# Sheet1.net
KiCad netlist of a schematic drawn in Altium Designer
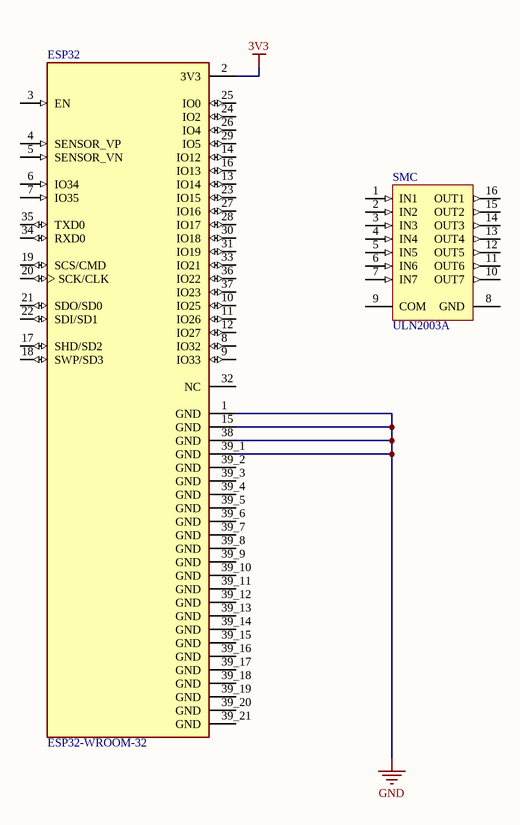
[diagram p0: Sheet1.SchDoc]

(export (version "E")
  (design (tool "Eeschema 10.0.6"))
  (components
    (comp (ref "ESP32")
      (value "ESP32-WROOM-32")
      (footprint "MODULE_ESP32-WROOM-32")
      (fields (field (name "MF") "Espressif Systems"))
      (libsource (lib "ESP32-WROOM-32") (part "ESP32-WROOM-32"))
    )
    (comp (ref "SMC")
      (value "ULN2003A")
      (footprint "STM-DIP-16L")
      (description "Seven Darlington Array, 50 V, 0.5 A, -40 to 85 degC, 16-Pin DIP, RoHS, Tube")
      (fields (field (name "MANUFACTURER") "STMicroelectronics"))
      (libsource (lib "Altium Content Vault") (part "STM-ULN2003A-PDIP-16"))
    )
  )
  (nets
    (net (code "1") (name "3V3") (class "Default")
      (node (ref "ESP32") (pin "2") (pinfunction "3V3_2") (pintype "power_in"))
    )
    (net (code "2") (name "GND") (class "Default")
      (node (ref "ESP32") (pin "1") (pinfunction "GND_1") (pintype "power_in"))
      (node (ref "ESP32") (pin "15") (pinfunction "GND_15") (pintype "power_in"))
      (node (ref "ESP32") (pin "38") (pinfunction "GND_38") (pintype "power_in"))
      (node (ref "ESP32") (pin "39_1") (pinfunction "GND_39_1") (pintype "power_in"))
    )
    (net (code "3") (name "unconnected-(ESP32-EN-Pad3)") (class "Default")
      (node (ref "ESP32") (pin "3") (pinfunction "EN_3") (pintype "input"))
    )
    (net (code "4") (name "unconnected-(ESP32-GND-Pad39_2)") (class "Default")
      (node (ref "ESP32") (pin "39_2") (pinfunction "GND_39_2") (pintype "power_in"))
    )
    (net (code "5") (name "unconnected-(ESP32-GND-Pad39_3)") (class "Default")
      (node (ref "ESP32") (pin "39_3") (pinfunction "GND_39_3") (pintype "power_in"))
    )
    (net (code "6") (name "unconnected-(ESP32-GND-Pad39_4)") (class "Default")
      (node (ref "ESP32") (pin "39_4") (pinfunction "GND_39_4") (pintype "power_in"))
    )
    (net (code "7") (name "unconnected-(ESP32-GND-Pad39_5)") (class "Default")
      (node (ref "ESP32") (pin "39_5") (pinfunction "GND_39_5") (pintype "power_in"))
    )
    (net (code "8") (name "unconnected-(ESP32-GND-Pad39_6)") (class "Default")
      (node (ref "ESP32") (pin "39_6") (pinfunction "GND_39_6") (pintype "power_in"))
    )
    (net (code "9") (name "unconnected-(ESP32-GND-Pad39_7)") (class "Default")
      (node (ref "ESP32") (pin "39_7") (pinfunction "GND_39_7") (pintype "power_in"))
    )
    (net (code "10") (name "unconnected-(ESP32-GND-Pad39_8)") (class "Default")
      (node (ref "ESP32") (pin "39_8") (pinfunction "GND_39_8") (pintype "power_in"))
    )
    (net (code "11") (name "unconnected-(ESP32-GND-Pad39_9)") (class "Default")
      (node (ref "ESP32") (pin "39_9") (pinfunction "GND_39_9") (pintype "power_in"))
    )
    (net (code "12") (name "unconnected-(ESP32-GND-Pad39_10)") (class "Default")
      (node (ref "ESP32") (pin "39_10") (pinfunction "GND_39_10") (pintype "power_in"))
    )
    (net (code "13") (name "unconnected-(ESP32-GND-Pad39_11)") (class "Default")
      (node (ref "ESP32") (pin "39_11") (pinfunction "GND_39_11") (pintype "power_in"))
    )
    (net (code "14") (name "unconnected-(ESP32-GND-Pad39_12)") (class "Default")
      (node (ref "ESP32") (pin "39_12") (pinfunction "GND_39_12") (pintype "power_in"))
    )
    (net (code "15") (name "unconnected-(ESP32-GND-Pad39_13)") (class "Default")
      (node (ref "ESP32") (pin "39_13") (pinfunction "GND_39_13") (pintype "power_in"))
    )
    (net (code "16") (name "unconnected-(ESP32-GND-Pad39_14)") (class "Default")
      (node (ref "ESP32") (pin "39_14") (pinfunction "GND_39_14") (pintype "power_in"))
    )
    (net (code "17") (name "unconnected-(ESP32-GND-Pad39_15)") (class "Default")
      (node (ref "ESP32") (pin "39_15") (pinfunction "GND_39_15") (pintype "power_in"))
    )
    (net (code "18") (name "unconnected-(ESP32-GND-Pad39_16)") (class "Default")
      (node (ref "ESP32") (pin "39_16") (pinfunction "GND_39_16") (pintype "power_in"))
    )
    (net (code "19") (name "unconnected-(ESP32-GND-Pad39_17)") (class "Default")
      (node (ref "ESP32") (pin "39_17") (pinfunction "GND_39_17") (pintype "power_in"))
    )
    (net (code "20") (name "unconnected-(ESP32-GND-Pad39_18)") (class "Default")
      (node (ref "ESP32") (pin "39_18") (pinfunction "GND_39_18") (pintype "power_in"))
    )
    (net (code "21") (name "unconnected-(ESP32-GND-Pad39_19)") (class "Default")
      (node (ref "ESP32") (pin "39_19") (pinfunction "GND_39_19") (pintype "power_in"))
    )
    (net (code "22") (name "unconnected-(ESP32-GND-Pad39_20)") (class "Default")
      (node (ref "ESP32") (pin "39_20") (pinfunction "GND_39_20") (pintype "power_in"))
    )
    (net (code "23") (name "unconnected-(ESP32-GND-Pad39_21)") (class "Default")
      (node (ref "ESP32") (pin "39_21") (pinfunction "GND_39_21") (pintype "power_in"))
    )
    (net (code "24") (name "unconnected-(ESP32-IO0-Pad25)") (class "Default")
      (node (ref "ESP32") (pin "25") (pinfunction "IO0_25") (pintype "bidirectional"))
    )
    (net (code "25") (name "unconnected-(ESP32-IO2-Pad24)") (class "Default")
      (node (ref "ESP32") (pin "24") (pinfunction "IO2_24") (pintype "bidirectional"))
    )
    (net (code "26") (name "unconnected-(ESP32-IO4-Pad26)") (class "Default")
      (node (ref "ESP32") (pin "26") (pinfunction "IO4_26") (pintype "bidirectional"))
    )
    (net (code "27") (name "unconnected-(ESP32-IO5-Pad29)") (class "Default")
      (node (ref "ESP32") (pin "29") (pinfunction "IO5_29") (pintype "bidirectional"))
    )
    (net (code "28") (name "unconnected-(ESP32-IO12-Pad14)") (class "Default")
      (node (ref "ESP32") (pin "14") (pinfunction "IO12_14") (pintype "bidirectional"))
    )
    (net (code "29") (name "unconnected-(ESP32-IO13-Pad16)") (class "Default")
      (node (ref "ESP32") (pin "16") (pinfunction "IO13_16") (pintype "bidirectional"))
    )
    (net (code "30") (name "unconnected-(ESP32-IO14-Pad13)") (class "Default")
      (node (ref "ESP32") (pin "13") (pinfunction "IO14_13") (pintype "bidirectional"))
    )
    (net (code "31") (name "unconnected-(ESP32-IO15-Pad23)") (class "Default")
      (node (ref "ESP32") (pin "23") (pinfunction "IO15_23") (pintype "bidirectional"))
    )
    (net (code "32") (name "unconnected-(ESP32-IO16-Pad27)") (class "Default")
      (node (ref "ESP32") (pin "27") (pinfunction "IO16_27") (pintype "bidirectional"))
    )
    (net (code "33") (name "unconnected-(ESP32-IO17-Pad28)") (class "Default")
      (node (ref "ESP32") (pin "28") (pinfunction "IO17_28") (pintype "bidirectional"))
    )
    (net (code "34") (name "unconnected-(ESP32-IO18-Pad30)") (class "Default")
      (node (ref "ESP32") (pin "30") (pinfunction "IO18_30") (pintype "bidirectional"))
    )
    (net (code "35") (name "unconnected-(ESP32-IO19-Pad31)") (class "Default")
      (node (ref "ESP32") (pin "31") (pinfunction "IO19_31") (pintype "bidirectional"))
    )
    (net (code "36") (name "unconnected-(ESP32-IO21-Pad33)") (class "Default")
      (node (ref "ESP32") (pin "33") (pinfunction "IO21_33") (pintype "bidirectional"))
    )
    (net (code "37") (name "unconnected-(ESP32-IO22-Pad36)") (class "Default")
      (node (ref "ESP32") (pin "36") (pinfunction "IO22_36") (pintype "bidirectional"))
    )
    (net (code "38") (name "unconnected-(ESP32-IO23-Pad37)") (class "Default")
      (node (ref "ESP32") (pin "37") (pinfunction "IO23_37") (pintype "bidirectional"))
    )
    (net (code "39") (name "unconnected-(ESP32-IO25-Pad10)") (class "Default")
      (node (ref "ESP32") (pin "10") (pinfunction "IO25_10") (pintype "bidirectional"))
    )
    (net (code "40") (name "unconnected-(ESP32-IO26-Pad11)") (class "Default")
      (node (ref "ESP32") (pin "11") (pinfunction "IO26_11") (pintype "bidirectional"))
    )
    (net (code "41") (name "unconnected-(ESP32-IO27-Pad12)") (class "Default")
      (node (ref "ESP32") (pin "12") (pinfunction "IO27_12") (pintype "bidirectional"))
    )
    (net (code "42") (name "unconnected-(ESP32-IO32-Pad8)") (class "Default")
      (node (ref "ESP32") (pin "8") (pinfunction "IO32_8") (pintype "bidirectional"))
    )
    (net (code "43") (name "unconnected-(ESP32-IO33-Pad9)") (class "Default")
      (node (ref "ESP32") (pin "9") (pinfunction "IO33_9") (pintype "bidirectional"))
    )
    (net (code "44") (name "unconnected-(ESP32-IO34-Pad6)") (class "Default")
      (node (ref "ESP32") (pin "6") (pinfunction "IO34_6") (pintype "input"))
    )
    (net (code "45") (name "unconnected-(ESP32-IO35-Pad7)") (class "Default")
      (node (ref "ESP32") (pin "7") (pinfunction "IO35_7") (pintype "input"))
    )
    (net (code "46") (name "unconnected-(ESP32-NC-Pad32)") (class "Default")
      (node (ref "ESP32") (pin "32") (pinfunction "NC_32") (pintype "passive"))
    )
    (net (code "47") (name "unconnected-(ESP32-RXD0-Pad34)") (class "Default")
      (node (ref "ESP32") (pin "34") (pinfunction "RXD0_34") (pintype "bidirectional"))
    )
    (net (code "48") (name "unconnected-(ESP32-SCK{slash}CLK-Pad20)") (class "Default")
      (node (ref "ESP32") (pin "20") (pinfunction "SCK/CLK_20") (pintype "bidirectional"))
    )
    (net (code "49") (name "unconnected-(ESP32-SCS{slash}CMD-Pad19)") (class "Default")
      (node (ref "ESP32") (pin "19") (pinfunction "SCS/CMD_19") (pintype "bidirectional"))
    )
    (net (code "50") (name "unconnected-(ESP32-SDI{slash}SD1-Pad22)") (class "Default")
      (node (ref "ESP32") (pin "22") (pinfunction "SDI/SD1_22") (pintype "bidirectional"))
    )
    (net (code "51") (name "unconnected-(ESP32-SDO{slash}SD0-Pad21)") (class "Default")
      (node (ref "ESP32") (pin "21") (pinfunction "SDO/SD0_21") (pintype "bidirectional"))
    )
    (net (code "52") (name "unconnected-(ESP32-SENSOR_VN-Pad5)") (class "Default")
      (node (ref "ESP32") (pin "5") (pinfunction "SENSOR_VN_5") (pintype "input"))
    )
    (net (code "53") (name "unconnected-(ESP32-SENSOR_VP-Pad4)") (class "Default")
      (node (ref "ESP32") (pin "4") (pinfunction "SENSOR_VP_4") (pintype "input"))
    )
    (net (code "54") (name "unconnected-(ESP32-SHD{slash}SD2-Pad17)") (class "Default")
      (node (ref "ESP32") (pin "17") (pinfunction "SHD/SD2_17") (pintype "bidirectional"))
    )
    (net (code "55") (name "unconnected-(ESP32-SWP{slash}SD3-Pad18)") (class "Default")
      (node (ref "ESP32") (pin "18") (pinfunction "SWP/SD3_18") (pintype "bidirectional"))
    )
    (net (code "56") (name "unconnected-(ESP32-TXD0-Pad35)") (class "Default")
      (node (ref "ESP32") (pin "35") (pinfunction "TXD0_35") (pintype "bidirectional"))
    )
    (net (code "57") (name "unconnected-(SMC-COM-Pad9)") (class "Default")
      (node (ref "SMC") (pin "9") (pinfunction "COM_9") (pintype "passive"))
    )
    (net (code "58") (name "unconnected-(SMC-GND-Pad8)") (class "Default")
      (node (ref "SMC") (pin "8") (pinfunction "GND_8") (pintype "power_in"))
    )
    (net (code "59") (name "unconnected-(SMC-IN1-Pad1)") (class "Default")
      (node (ref "SMC") (pin "1") (pinfunction "IN1_1") (pintype "input"))
    )
    (net (code "60") (name "unconnected-(SMC-IN2-Pad2)") (class "Default")
      (node (ref "SMC") (pin "2") (pinfunction "IN2_2") (pintype "input"))
    )
    (net (code "61") (name "unconnected-(SMC-IN3-Pad3)") (class "Default")
      (node (ref "SMC") (pin "3") (pinfunction "IN3_3") (pintype "input"))
    )
    (net (code "62") (name "unconnected-(SMC-IN4-Pad4)") (class "Default")
      (node (ref "SMC") (pin "4") (pinfunction "IN4_4") (pintype "input"))
    )
    (net (code "63") (name "unconnected-(SMC-IN5-Pad5)") (class "Default")
      (node (ref "SMC") (pin "5") (pinfunction "IN5_5") (pintype "input"))
    )
    (net (code "64") (name "unconnected-(SMC-IN6-Pad6)") (class "Default")
      (node (ref "SMC") (pin "6") (pinfunction "IN6_6") (pintype "input"))
    )
    (net (code "65") (name "unconnected-(SMC-IN7-Pad7)") (class "Default")
      (node (ref "SMC") (pin "7") (pinfunction "IN7_7") (pintype "input"))
    )
    (net (code "66") (name "unconnected-(SMC-OUT1-Pad16)") (class "Default")
      (node (ref "SMC") (pin "16") (pinfunction "OUT1_16") (pintype "output"))
    )
    (net (code "67") (name "unconnected-(SMC-OUT2-Pad15)") (class "Default")
      (node (ref "SMC") (pin "15") (pinfunction "OUT2_15") (pintype "output"))
    )
    (net (code "68") (name "unconnected-(SMC-OUT3-Pad14)") (class "Default")
      (node (ref "SMC") (pin "14") (pinfunction "OUT3_14") (pintype "output"))
    )
    (net (code "69") (name "unconnected-(SMC-OUT4-Pad13)") (class "Default")
      (node (ref "SMC") (pin "13") (pinfunction "OUT4_13") (pintype "output"))
    )
    (net (code "70") (name "unconnected-(SMC-OUT5-Pad12)") (class "Default")
      (node (ref "SMC") (pin "12") (pinfunction "OUT5_12") (pintype "output"))
    )
    (net (code "71") (name "unconnected-(SMC-OUT6-Pad11)") (class "Default")
      (node (ref "SMC") (pin "11") (pinfunction "OUT6_11") (pintype "output"))
    )
    (net (code "72") (name "unconnected-(SMC-OUT7-Pad10)") (class "Default")
      (node (ref "SMC") (pin "10") (pinfunction "OUT7_10") (pintype "output"))
    )
  )
)
